# 07_POWER.net
KiCad netlist of a schematic drawn in Altium Designer
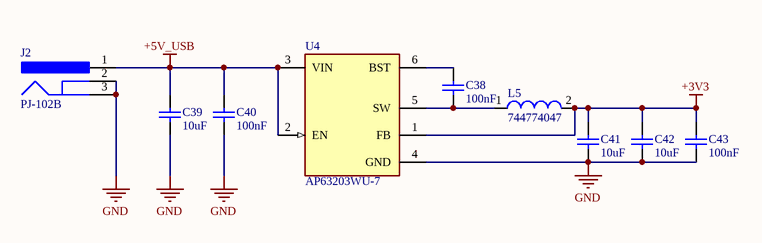
[diagram p0: 07. POWER.SchDoc]

(export (version "E")
  (design (tool "Eeschema 10.0.6"))
  (components
    (comp (ref "C38")
      (value "100nF")
      (footprint "CAPC1005X56X25NL10T15")
      (fields
        (field (name "MANUFACTURER") "AVX Interconnect / Elco")
        (field (name "PART NUMBER") "04026D104KAT2A")
      )
      (libsource (lib "Altium Content Vault") (part "CAP"))
    )
    (comp (ref "C39")
      (value "10uF")
      (footprint "CAPC1608X90X35NL10T15")
      (fields (field (name "MANUFACTURER") "Murata") (field (name "PART NUMBER") "GCM188R70J225KE22D"))
      (libsource (lib "Altium Content Vault") (part "CAP"))
    )
    (comp (ref "C40")
      (value "100nF")
      (footprint "CAPC1005X56X25NL10T15")
      (fields
        (field (name "MANUFACTURER") "AVX Interconnect / Elco")
        (field (name "PART NUMBER") "04026D104KAT2A")
      )
      (libsource (lib "Altium Content Vault") (part "CAP"))
    )
    (comp (ref "C41")
      (value "10uF")
      (footprint "CAPC1608X90X35NL10T15")
      (fields (field (name "MANUFACTURER") "Murata") (field (name "PART NUMBER") "GCM188R70J225KE22D"))
      (libsource (lib "Altium Content Vault") (part "CAP"))
    )
    (comp (ref "C42")
      (value "10uF")
      (footprint "CAPC1608X90X35NL10T15")
      (fields (field (name "MANUFACTURER") "Murata") (field (name "PART NUMBER") "GCM188R70J225KE22D"))
      (libsource (lib "Altium Content Vault") (part "CAP"))
    )
    (comp (ref "C43")
      (value "100nF")
      (footprint "CAPC1005X56X25NL10T15")
      (fields
        (field (name "MANUFACTURER") "AVX Interconnect / Elco")
        (field (name "PART NUMBER") "04026D104KAT2A")
      )
      (libsource (lib "Altium Content Vault") (part "CAP"))
    )
    (comp (ref "J2")
      (value "PJ-102B")
      (footprint "CUI-PJ-102B_V")
      (fields (field (name "MANUFACTURER") "CUIInc."))
      (libsource (lib "Altium Content Vault") (part "JACK-2CD3-RN"))
    )
    (comp (ref "L5")
      (value "744774047")
      (footprint "WE-PD2-M")
      (description "SMD Power Inductor WE-PD2, L = 4.70 µH")
      (libsource (lib "Altium Content Vault") (part "PAS-IND-INDUCTOR-2"))
    )
    (comp (ref "U4")
      (value "AP63203WU-7")
      (footprint "FP-TSOT26-IPC_B")
      (description "IC REG BUCK 3.3V 2A TSOT26")
      (fields
        (field (name "MANUFACTURER") "Diodes Inc.")
        (field (name "OCTOPART") "https://octopart.com/ap63203wu-7-diodes+inc.-98099550")
      )
      (libsource (lib "Altium Content Vault") (part "0e61c2974d7114b43f01ef96ae2e524"))
    )
  )
  (nets
    (net (code "1") (name "+3V3") (class "Default")
      (node (ref "C41") (pin "2") (pinfunction "2_2") (pintype "passive"))
      (node (ref "C42") (pin "2") (pinfunction "2_2") (pintype "passive"))
      (node (ref "C43") (pin "2") (pinfunction "2_2") (pintype "passive"))
      (node (ref "L5") (pin "2") (pinfunction "2_2") (pintype "passive"))
      (node (ref "U4") (pin "1") (pinfunction "FB_1") (pintype "passive"))
    )
    (net (code "2") (name "+5V_USB") (class "Default")
      (node (ref "C39") (pin "2") (pinfunction "2_2") (pintype "passive"))
      (node (ref "C40") (pin "2") (pinfunction "2_2") (pintype "passive"))
      (node (ref "J2") (pin "1") (pinfunction "1_1") (pintype "passive"))
      (node (ref "U4") (pin "2") (pinfunction "EN_2") (pintype "input"))
      (node (ref "U4") (pin "3") (pinfunction "VIN_3") (pintype "power_in"))
    )
    (net (code "3") (name "GND") (class "Default")
      (node (ref "C39") (pin "1") (pinfunction "1_1") (pintype "passive"))
      (node (ref "C40") (pin "1") (pinfunction "1_1") (pintype "passive"))
      (node (ref "C41") (pin "1") (pinfunction "1_1") (pintype "passive"))
      (node (ref "C42") (pin "1") (pinfunction "1_1") (pintype "passive"))
      (node (ref "C43") (pin "1") (pinfunction "1_1") (pintype "passive"))
      (node (ref "J2") (pin "2") (pinfunction "2_2") (pintype "passive"))
      (node (ref "J2") (pin "3") (pinfunction "3_3") (pintype "passive"))
      (node (ref "U4") (pin "4") (pinfunction "GND_4") (pintype "power_in"))
    )
    (net (code "4") (name "Net-(U4-BST)") (class "Default")
      (node (ref "C38") (pin "2") (pinfunction "2_2") (pintype "passive"))
      (node (ref "U4") (pin "6") (pinfunction "BST_6") (pintype "passive"))
    )
    (net (code "5") (name "Net-(U4-SW)") (class "Default")
      (node (ref "C38") (pin "1") (pinfunction "1_1") (pintype "passive"))
      (node (ref "L5") (pin "1") (pinfunction "1_1") (pintype "passive"))
      (node (ref "U4") (pin "5") (pinfunction "SW_5") (pintype "passive"))
    )
  )
)
